# FrigoTemp.net
KiCad netlist of a schematic drawn in EAGLE
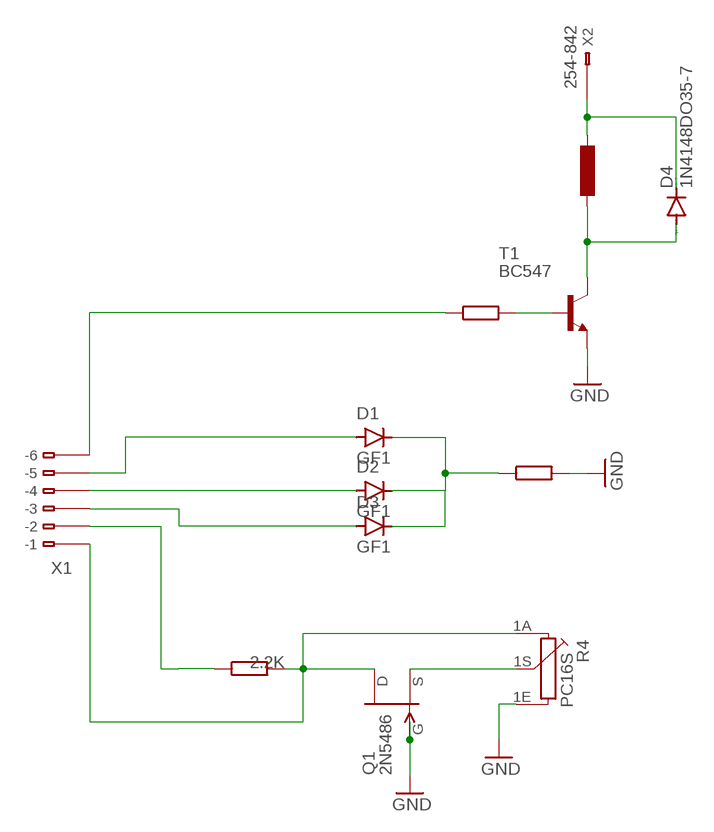
[diagram p0: schematic, sheet 1]

(export (version "E")
  (design (tool "Eeschema 10.0.6"))
  (components
    (comp (ref "D1")
      (value "GF1")
      (footprint "eagle-import:SMA-DO214AC")
      (libsource (lib "eagle-import") (part "GF1"))
    )
    (comp (ref "D2")
      (value "GF1")
      (footprint "eagle-import:SMA-DO214AC")
      (libsource (lib "eagle-import") (part "GF1"))
    )
    (comp (ref "D3")
      (value "GF1")
      (footprint "eagle-import:SMA-DO214AC")
      (libsource (lib "eagle-import") (part "GF1"))
    )
    (comp (ref "D4")
      (value "1N4148DO35-7")
      (footprint "eagle-import:DO35-7")
      (libsource (lib "eagle-import") (part "1N4148DO35-7"))
    )
    (comp (ref "Q1")
      (value "2N5486")
      (footprint "eagle-import:TO92-")
      (libsource (lib "eagle-import") (part "?5482N6"))
    )
    (comp (ref "R4")
      (value "PC16S")
      (footprint "eagle-import:PC16S")
      (libsource (lib "eagle-import") (part "PC16S"))
    )
    (comp (ref "T1")
      (value "BC547")
      (footprint "eagle-import:TO92")
      (libsource (lib "eagle-import") (part "BC547"))
    )
    (comp (ref "X1")
      (value "233-106")
      (footprint "eagle-import:233-106")
      (libsource (lib "eagle-import") (part "233-106"))
    )
    (comp (ref "X2")
      (value "254-842")
      (footprint "eagle-import:254-842")
      (libsource (lib "eagle-import") (part "254-842"))
    )
  )
  (nets
    (net (code "1") (name "GND") (class "Default")
      (node (ref "Q1") (pin "1") (pinfunction "G_1") (pintype "passive"))
      (node (ref "R4") (pin "1E") (pinfunction "1E_1E") (pintype "passive"))
      (node (ref "T1") (pin "1") (pinfunction "E_1") (pintype "passive"))
    )
    (net (code "2") (name "Net-(D1-C)") (class "Default")
      (node (ref "D1") (pin "K") (pinfunction "C_K") (pintype "passive"))
      (node (ref "D2") (pin "K") (pinfunction "C_K") (pintype "passive"))
      (node (ref "D3") (pin "K") (pinfunction "C_K") (pintype "passive"))
    )
    (net (code "3") (name "Net-(Q1-D)") (class "Default")
      (node (ref "Q1") (pin "3") (pinfunction "D_3") (pintype "passive"))
      (node (ref "R4") (pin "1A") (pinfunction "1A_1A") (pintype "passive"))
      (node (ref "X1") (pin "B1") (pinfunction "B-1_B1") (pintype "passive"))
    )
    (net (code "4") (name "Net-(Q1-S)") (class "Default")
      (node (ref "Q1") (pin "2") (pinfunction "S_2") (pintype "passive"))
      (node (ref "R4") (pin "1S") (pinfunction "1S_1S") (pintype "passive"))
    )
    (net (code "5") (name "Net-(T1-C)") (class "Default")
      (node (ref "D4") (pin "A") (pinfunction "A_A") (pintype "passive"))
      (node (ref "T1") (pin "3") (pinfunction "C_3") (pintype "passive"))
    )
    (net (code "6") (name "Net-(X1-B-3)") (class "Default")
      (node (ref "D3") (pin "A") (pinfunction "A_A") (pintype "passive"))
      (node (ref "X1") (pin "B3") (pinfunction "B-3_B3") (pintype "passive"))
    )
    (net (code "7") (name "Net-(X1-B-4)") (class "Default")
      (node (ref "D2") (pin "A") (pinfunction "A_A") (pintype "passive"))
      (node (ref "X1") (pin "B4") (pinfunction "B-4_B4") (pintype "passive"))
    )
    (net (code "8") (name "Net-(X1-B-5)") (class "Default")
      (node (ref "D1") (pin "A") (pinfunction "A_A") (pintype "passive"))
      (node (ref "X1") (pin "B5") (pinfunction "B-5_B5") (pintype "passive"))
    )
    (net (code "9") (name "Net-(X2-B1)") (class "Default")
      (node (ref "D4") (pin "C") (pinfunction "C_C") (pintype "passive"))
      (node (ref "X2") (pin "1@2") (pinfunction "B1_1@2") (pintype "passive"))
    )
    (net (code "10") (name "unconnected-(T1-B-Pad2)") (class "Default")
      (node (ref "T1") (pin "2") (pinfunction "B_2") (pintype "passive"))
    )
    (net (code "11") (name "unconnected-(X1--1-PadA1)") (class "Default")
      (node (ref "X1") (pin "A1") (pinfunction "-1_A1") (pintype "passive"))
    )
    (net (code "12") (name "unconnected-(X1--2-PadA2)") (class "Default")
      (node (ref "X1") (pin "A2") (pinfunction "-2_A2") (pintype "passive"))
    )
    (net (code "13") (name "unconnected-(X1--3-PadA3)") (class "Default")
      (node (ref "X1") (pin "A3") (pinfunction "-3_A3") (pintype "passive"))
    )
    (net (code "14") (name "unconnected-(X1--4-PadA4)") (class "Default")
      (node (ref "X1") (pin "A4") (pinfunction "-4_A4") (pintype "passive"))
    )
    (net (code "15") (name "unconnected-(X1--5-PadA5)") (class "Default")
      (node (ref "X1") (pin "A5") (pinfunction "-5_A5") (pintype "passive"))
    )
    (net (code "16") (name "unconnected-(X1--6-PadA6)") (class "Default")
      (node (ref "X1") (pin "A6") (pinfunction "-6_A6") (pintype "passive"))
    )
    (net (code "17") (name "unconnected-(X1-B-2-PadB2)") (class "Default")
      (node (ref "X1") (pin "B2") (pinfunction "B-2_B2") (pintype "passive"))
    )
    (net (code "18") (name "unconnected-(X1-B-6-PadB6)") (class "Default")
      (node (ref "X1") (pin "B6") (pinfunction "B-6_B6") (pintype "passive"))
    )
    (net (code "19") (name "unconnected-(X2-A1-Pad1@1)") (class "Default")
      (node (ref "X2") (pin "1@1") (pinfunction "A1_1@1") (pintype "passive"))
    )
  )
)
